# GSM_Link_12_Power.net
KiCad netlist of a schematic drawn in Altium Designer
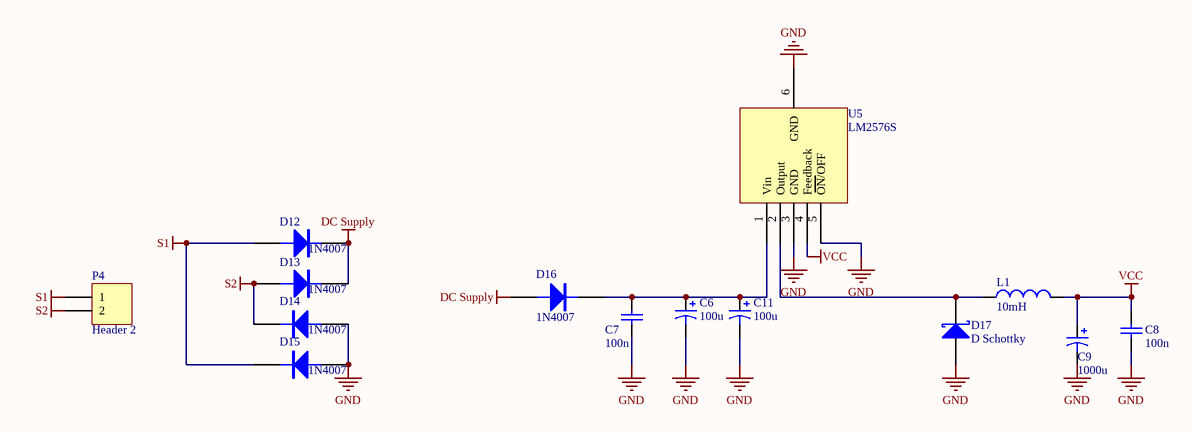
[diagram p0: GSM_Link_12_Power.SchDoc]

(export (version "E")
  (design (tool "Eeschema 10.0.6"))
  (components
    (comp (ref "C6")
      (value "100u")
      (footprint "RB.2/.4_p")
      (description "Polarized Capacitor (Radial)")
      (fields (field (name "PUBLISHER") "Altium Limited"))
      (libsource (lib "Miscellaneous Devices") (part "Cap Pol1"))
    )
    (comp (ref "C7")
      (value "100n")
      (footprint "0805_smd")
      (description "Capacitor")
      (fields (field (name "PUBLISHER") "Altium Limited"))
      (libsource (lib "Miscellaneous Devices") (part "Cap"))
    )
    (comp (ref "C8")
      (value "100n")
      (footprint "0805_smd")
      (description "Capacitor")
      (fields (field (name "PUBLISHER") "Altium Limited"))
      (libsource (lib "Miscellaneous Devices") (part "Cap"))
    )
    (comp (ref "C9")
      (value "1000u")
      (footprint "RB.2/.4_p")
      (description "Polarized Capacitor (Radial)")
      (fields (field (name "PUBLISHER") "Altium Limited"))
      (libsource (lib "Miscellaneous Devices") (part "Cap Pol1"))
    )
    (comp (ref "C11")
      (value "100u")
      (footprint "RB.1/.2_P")
      (description "Polarized Capacitor (Radial)")
      (fields (field (name "PUBLISHER") "Altium Limited"))
      (libsource (lib "Miscellaneous Devices") (part "Cap Pol1"))
    )
    (comp (ref "D12")
      (value "1N4007")
      (footprint "7227_SMD")
      (description "Diode")
      (libsource (lib "*") (part "DIODE"))
    )
    (comp (ref "D13")
      (value "1N4007")
      (footprint "7227_SMD")
      (description "Diode")
      (libsource (lib "*") (part "DIODE"))
    )
    (comp (ref "D14")
      (value "1N4007")
      (footprint "7227_SMD")
      (description "Diode")
      (libsource (lib "*") (part "DIODE"))
    )
    (comp (ref "D15")
      (value "1N4007")
      (footprint "7227_SMD")
      (description "Diode")
      (libsource (lib "*") (part "DIODE"))
    )
    (comp (ref "D16")
      (value "1N4007")
      (footprint "7227_SMD")
      (description "Diode")
      (libsource (lib "*") (part "DIODE"))
    )
    (comp (ref "D17")
      (value "D Schottky")
      (footprint "7227_SMD")
      (description "Schottky Diode")
      (fields (field (name "PUBLISHER") "Altium Limited"))
      (libsource (lib "Miscellaneous Devices") (part "D Schottky"))
    )
    (comp (ref "L1")
      (value "10mH")
      (footprint "RB.2/.4")
      (description "Inductor")
      (fields (field (name "PUBLISHER") "Altium Limited"))
      (libsource (lib "Miscellaneous Devices") (part "Inductor"))
    )
    (comp (ref "P4")
      (value "Header 2")
      (footprint "PCON_2")
      (description "Header, 2-Pin")
      (fields (field (name "PUBLISHER") "Altium Limited"))
      (libsource (lib "Miscellaneous Connectors") (part "Header 2"))
    )
    (comp (ref "U5")
      (value "LM2576S")
      (footprint "D2PAK_SMD")
      (libsource (lib "BNB_Altium_LIB_004") (part "LM2576S"))
    )
  )
  (nets
    (net (code "1") (name "DC Supply") (class "Default")
      (node (ref "D12") (pin "K") (pinfunction "2_K") (pintype "passive"))
      (node (ref "D13") (pin "K") (pinfunction "2_K") (pintype "passive"))
      (node (ref "D16") (pin "A") (pinfunction "1_A") (pintype "passive"))
    )
    (net (code "2") (name "GND") (class "Default")
      (node (ref "C11") (pin "2") (pinfunction "2_2") (pintype "passive"))
      (node (ref "C6") (pin "2") (pinfunction "2_2") (pintype "passive"))
      (node (ref "C7") (pin "1") (pinfunction "1_1") (pintype "passive"))
      (node (ref "C8") (pin "1") (pinfunction "1_1") (pintype "passive"))
      (node (ref "C9") (pin "2") (pinfunction "2_2") (pintype "passive"))
      (node (ref "D14") (pin "A") (pinfunction "1_A") (pintype "passive"))
      (node (ref "D15") (pin "A") (pinfunction "1_A") (pintype "passive"))
      (node (ref "D17") (pin "A") (pinfunction "A_A") (pintype "passive"))
      (node (ref "U5") (pin "3") (pinfunction "GND_3") (pintype "passive"))
      (node (ref "U5") (pin "5") (pinfunction "ON/OFF_5") (pintype "passive"))
      (node (ref "U5") (pin "6") (pinfunction "GND_6") (pintype "passive"))
    )
    (net (code "3") (name "Net-(D16-2)") (class "Default")
      (node (ref "C11") (pin "1") (pinfunction "1_1") (pintype "passive"))
      (node (ref "C6") (pin "1") (pinfunction "1_1") (pintype "passive"))
      (node (ref "C7") (pin "2") (pinfunction "2_2") (pintype "passive"))
      (node (ref "D16") (pin "K") (pinfunction "2_K") (pintype "passive"))
      (node (ref "U5") (pin "1") (pinfunction "Vin_1") (pintype "passive"))
    )
    (net (code "4") (name "Net-(U5-Output)") (class "Default")
      (node (ref "D17") (pin "K") (pinfunction "K_K") (pintype "passive"))
      (node (ref "L1") (pin "1") (pinfunction "1_1") (pintype "passive"))
      (node (ref "U5") (pin "2") (pinfunction "Output_2") (pintype "passive"))
    )
    (net (code "5") (name "S1") (class "Default")
      (node (ref "D12") (pin "A") (pinfunction "1_A") (pintype "passive"))
      (node (ref "D15") (pin "K") (pinfunction "2_K") (pintype "passive"))
      (node (ref "P4") (pin "1") (pinfunction "1_1") (pintype "passive"))
    )
    (net (code "6") (name "S2") (class "Default")
      (node (ref "D13") (pin "A") (pinfunction "1_A") (pintype "passive"))
      (node (ref "D14") (pin "K") (pinfunction "2_K") (pintype "passive"))
      (node (ref "P4") (pin "2") (pinfunction "2_2") (pintype "passive"))
    )
    (net (code "7") (name "VCC") (class "Default")
      (node (ref "C8") (pin "2") (pinfunction "2_2") (pintype "passive"))
      (node (ref "C9") (pin "1") (pinfunction "1_1") (pintype "passive"))
      (node (ref "L1") (pin "2") (pinfunction "2_2") (pintype "passive"))
      (node (ref "U5") (pin "4") (pinfunction "Feedback_4") (pintype "passive"))
    )
  )
)
